# PCA9955BTW.net
KiCad netlist of a schematic drawn in EAGLE
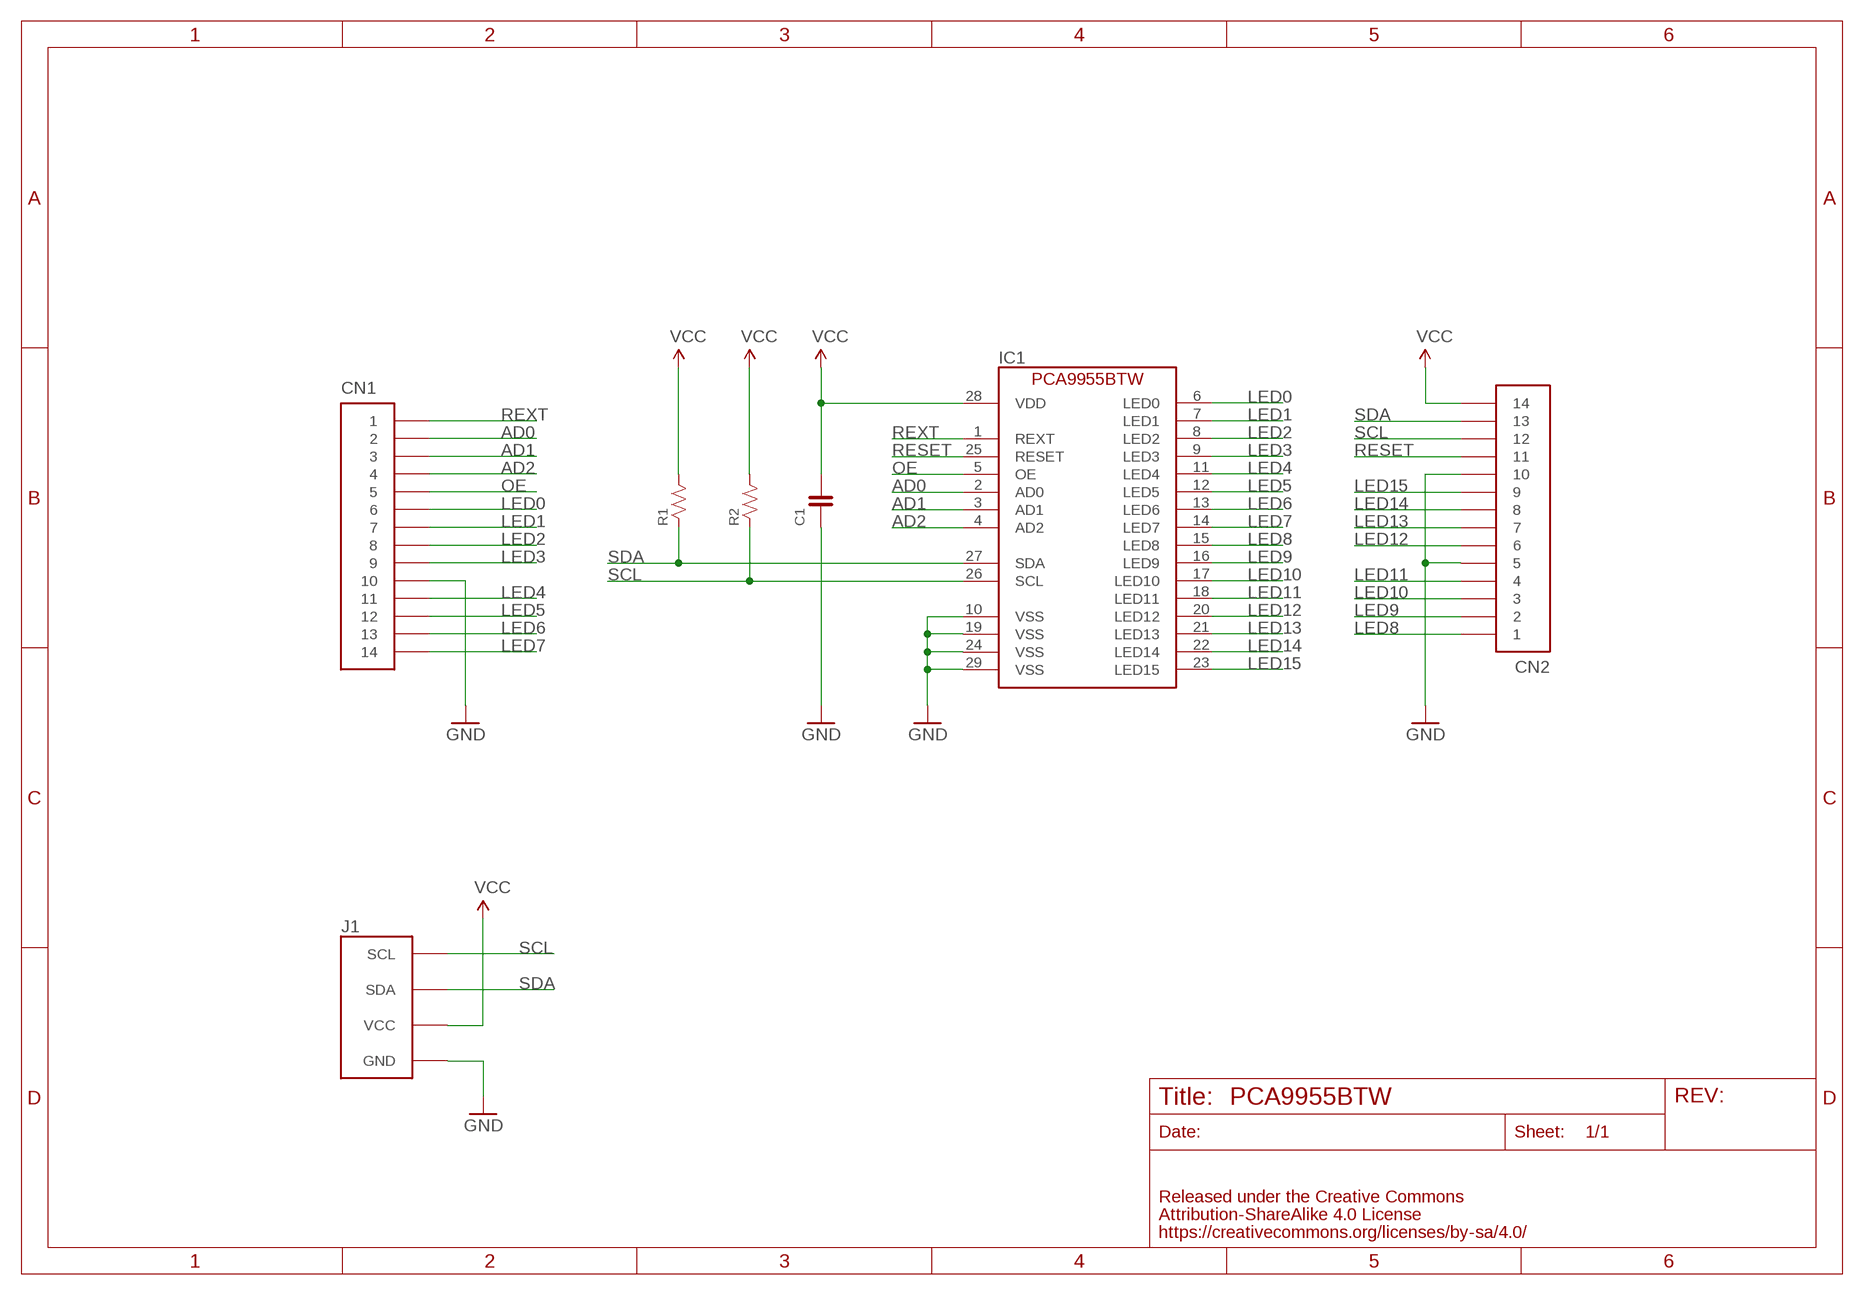
[diagram p0: schematic, sheet 1]

(export (version "E")
  (design (tool "Eeschema 10.0.6"))
  (components
    (comp (ref "C1")
      (value "CAPACITOR-0603")
      (footprint "eagle-import:0603")
      (libsource (lib "eagle-import") (part "CAPACITOR-0603"))
    )
    (comp (ref "CN1")
      (value "PIN_HEADER_1X14")
      (footprint "eagle-import:PIN_1X14_SNEAKY")
      (libsource (lib "eagle-import") (part "PIN_HEADER_1X14"))
    )
    (comp (ref "CN2")
      (value "PIN_HEADER_1X14")
      (footprint "eagle-import:PIN_1X14_SNEAKY")
      (libsource (lib "eagle-import") (part "PIN_HEADER_1X14"))
    )
    (comp (ref "IC1")
      (value "PCA9955BTW")
      (footprint "eagle-import:HTSSOP28")
      (libsource (lib "eagle-import") (part "PCA9955BTW"))
    )
    (comp (ref "J1")
      (value "FABO_BRICK_I2C-CONNECTOR")
      (footprint "eagle-import:FABO_BRICK_I2C_CONNECTOR")
      (libsource (lib "eagle-import") (part "FABO_BRICK_I2C-CONNECTOR"))
    )
    (comp (ref "R1")
      (value "RESISTOR-0603")
      (footprint "eagle-import:0603")
      (libsource (lib "eagle-import") (part "RESISTOR-0603"))
    )
    (comp (ref "R2")
      (value "RESISTOR-0603")
      (footprint "eagle-import:0603")
      (libsource (lib "eagle-import") (part "RESISTOR-0603"))
    )
  )
  (nets
    (net (code "1") (name "/AD0") (class "Default")
      (node (ref "CN1") (pin "2") (pinfunction "2_2") (pintype "bidirectional"))
      (node (ref "IC1") (pin "2") (pinfunction "AD0_2") (pintype "bidirectional"))
    )
    (net (code "2") (name "/AD1") (class "Default")
      (node (ref "CN1") (pin "3") (pinfunction "3_3") (pintype "bidirectional"))
      (node (ref "IC1") (pin "3") (pinfunction "AD1_3") (pintype "bidirectional"))
    )
    (net (code "3") (name "/AD2") (class "Default")
      (node (ref "CN1") (pin "4") (pinfunction "4_4") (pintype "bidirectional"))
      (node (ref "IC1") (pin "4") (pinfunction "AD2_4") (pintype "bidirectional"))
    )
    (net (code "4") (name "/LED0") (class "Default")
      (node (ref "CN1") (pin "6") (pinfunction "6_6") (pintype "bidirectional"))
      (node (ref "IC1") (pin "6") (pinfunction "LED0_6") (pintype "bidirectional"))
    )
    (net (code "5") (name "/LED1") (class "Default")
      (node (ref "CN1") (pin "7") (pinfunction "7_7") (pintype "bidirectional"))
      (node (ref "IC1") (pin "7") (pinfunction "LED1_7") (pintype "bidirectional"))
    )
    (net (code "6") (name "/LED2") (class "Default")
      (node (ref "CN1") (pin "8") (pinfunction "8_8") (pintype "bidirectional"))
      (node (ref "IC1") (pin "8") (pinfunction "LED2_8") (pintype "bidirectional"))
    )
    (net (code "7") (name "/LED3") (class "Default")
      (node (ref "CN1") (pin "9") (pinfunction "9_9") (pintype "bidirectional"))
      (node (ref "IC1") (pin "9") (pinfunction "LED3_9") (pintype "bidirectional"))
    )
    (net (code "8") (name "/LED4") (class "Default")
      (node (ref "CN1") (pin "11") (pinfunction "11_11") (pintype "bidirectional"))
      (node (ref "IC1") (pin "11") (pinfunction "LED4_11") (pintype "bidirectional"))
    )
    (net (code "9") (name "/LED5") (class "Default")
      (node (ref "CN1") (pin "12") (pinfunction "12_12") (pintype "bidirectional"))
      (node (ref "IC1") (pin "12") (pinfunction "LED5_12") (pintype "bidirectional"))
    )
    (net (code "10") (name "/LED6") (class "Default")
      (node (ref "CN1") (pin "13") (pinfunction "13_13") (pintype "bidirectional"))
      (node (ref "IC1") (pin "13") (pinfunction "LED6_13") (pintype "bidirectional"))
    )
    (net (code "11") (name "/LED7") (class "Default")
      (node (ref "CN1") (pin "14") (pinfunction "14_14") (pintype "bidirectional"))
      (node (ref "IC1") (pin "14") (pinfunction "LED7_14") (pintype "bidirectional"))
    )
    (net (code "12") (name "/LED8") (class "Default")
      (node (ref "CN2") (pin "1") (pinfunction "1_1") (pintype "bidirectional"))
      (node (ref "IC1") (pin "15") (pinfunction "LED8_15") (pintype "bidirectional"))
    )
    (net (code "13") (name "/LED9") (class "Default")
      (node (ref "CN2") (pin "2") (pinfunction "2_2") (pintype "bidirectional"))
      (node (ref "IC1") (pin "16") (pinfunction "LED9_16") (pintype "bidirectional"))
    )
    (net (code "14") (name "/LED10") (class "Default")
      (node (ref "CN2") (pin "3") (pinfunction "3_3") (pintype "bidirectional"))
      (node (ref "IC1") (pin "17") (pinfunction "LED10_17") (pintype "bidirectional"))
    )
    (net (code "15") (name "/LED11") (class "Default")
      (node (ref "CN2") (pin "4") (pinfunction "4_4") (pintype "bidirectional"))
      (node (ref "IC1") (pin "18") (pinfunction "LED11_18") (pintype "bidirectional"))
    )
    (net (code "16") (name "/LED12") (class "Default")
      (node (ref "CN2") (pin "6") (pinfunction "6_6") (pintype "bidirectional"))
      (node (ref "IC1") (pin "20") (pinfunction "LED12_20") (pintype "bidirectional"))
    )
    (net (code "17") (name "/LED13") (class "Default")
      (node (ref "CN2") (pin "7") (pinfunction "7_7") (pintype "bidirectional"))
      (node (ref "IC1") (pin "21") (pinfunction "LED13_21") (pintype "bidirectional"))
    )
    (net (code "18") (name "/LED14") (class "Default")
      (node (ref "CN2") (pin "8") (pinfunction "8_8") (pintype "bidirectional"))
      (node (ref "IC1") (pin "22") (pinfunction "LED14_22") (pintype "bidirectional"))
    )
    (net (code "19") (name "/LED15") (class "Default")
      (node (ref "CN2") (pin "9") (pinfunction "9_9") (pintype "bidirectional"))
      (node (ref "IC1") (pin "23") (pinfunction "LED15_23") (pintype "bidirectional"))
    )
    (net (code "20") (name "/OE") (class "Default")
      (node (ref "CN1") (pin "5") (pinfunction "5_5") (pintype "bidirectional"))
      (node (ref "IC1") (pin "5") (pinfunction "OE_5") (pintype "bidirectional"))
    )
    (net (code "21") (name "/RESET") (class "Default")
      (node (ref "CN2") (pin "11") (pinfunction "11_11") (pintype "bidirectional"))
      (node (ref "IC1") (pin "25") (pinfunction "RESET_25") (pintype "bidirectional"))
    )
    (net (code "22") (name "/REXT") (class "Default")
      (node (ref "CN1") (pin "1") (pinfunction "1_1") (pintype "bidirectional"))
      (node (ref "IC1") (pin "1") (pinfunction "REXT_1") (pintype "bidirectional"))
    )
    (net (code "23") (name "/SCL") (class "Default")
      (node (ref "CN2") (pin "12") (pinfunction "12_12") (pintype "bidirectional"))
      (node (ref "IC1") (pin "26") (pinfunction "SCL_26") (pintype "bidirectional"))
      (node (ref "J1") (pin "SCL") (pinfunction "SCL_SCL") (pintype "bidirectional"))
      (node (ref "R2") (pin "1") (pinfunction "1_1") (pintype "bidirectional"))
    )
    (net (code "24") (name "/SDA") (class "Default")
      (node (ref "CN2") (pin "13") (pinfunction "13_13") (pintype "bidirectional"))
      (node (ref "IC1") (pin "27") (pinfunction "SDA_27") (pintype "bidirectional"))
      (node (ref "J1") (pin "SDA") (pinfunction "SDA_SDA") (pintype "bidirectional"))
      (node (ref "R1") (pin "1") (pinfunction "1_1") (pintype "bidirectional"))
    )
    (net (code "25") (name "GND") (class "Default")
      (node (ref "C1") (pin "1") (pinfunction "1_1") (pintype "passive"))
      (node (ref "CN1") (pin "10") (pinfunction "10_10") (pintype "bidirectional"))
      (node (ref "CN2") (pin "10") (pinfunction "10_10") (pintype "bidirectional"))
      (node (ref "CN2") (pin "5") (pinfunction "5_5") (pintype "bidirectional"))
      (node (ref "IC1") (pin "10") (pinfunction "VSS_10") (pintype "bidirectional"))
      (node (ref "IC1") (pin "19") (pinfunction "VSS_19") (pintype "bidirectional"))
      (node (ref "IC1") (pin "24") (pinfunction "VSS_24") (pintype "bidirectional"))
      (node (ref "IC1") (pin "29") (pinfunction "VSS_29") (pintype "bidirectional"))
      (node (ref "J1") (pin "GND") (pinfunction "GND_GND") (pintype "bidirectional"))
    )
    (net (code "26") (name "VCC") (class "Default")
      (node (ref "C1") (pin "2") (pinfunction "2_2") (pintype "passive"))
      (node (ref "CN2") (pin "14") (pinfunction "14_14") (pintype "bidirectional"))
      (node (ref "IC1") (pin "28") (pinfunction "VDD_28") (pintype "bidirectional"))
      (node (ref "J1") (pin "VCC") (pinfunction "VCC_VCC") (pintype "bidirectional"))
      (node (ref "R1") (pin "2") (pinfunction "2_2") (pintype "bidirectional"))
      (node (ref "R2") (pin "2") (pinfunction "2_2") (pintype "bidirectional"))
    )
  )
)
